# bare_ESP-mainboard.net
KiCad netlist of a schematic drawn in EAGLE
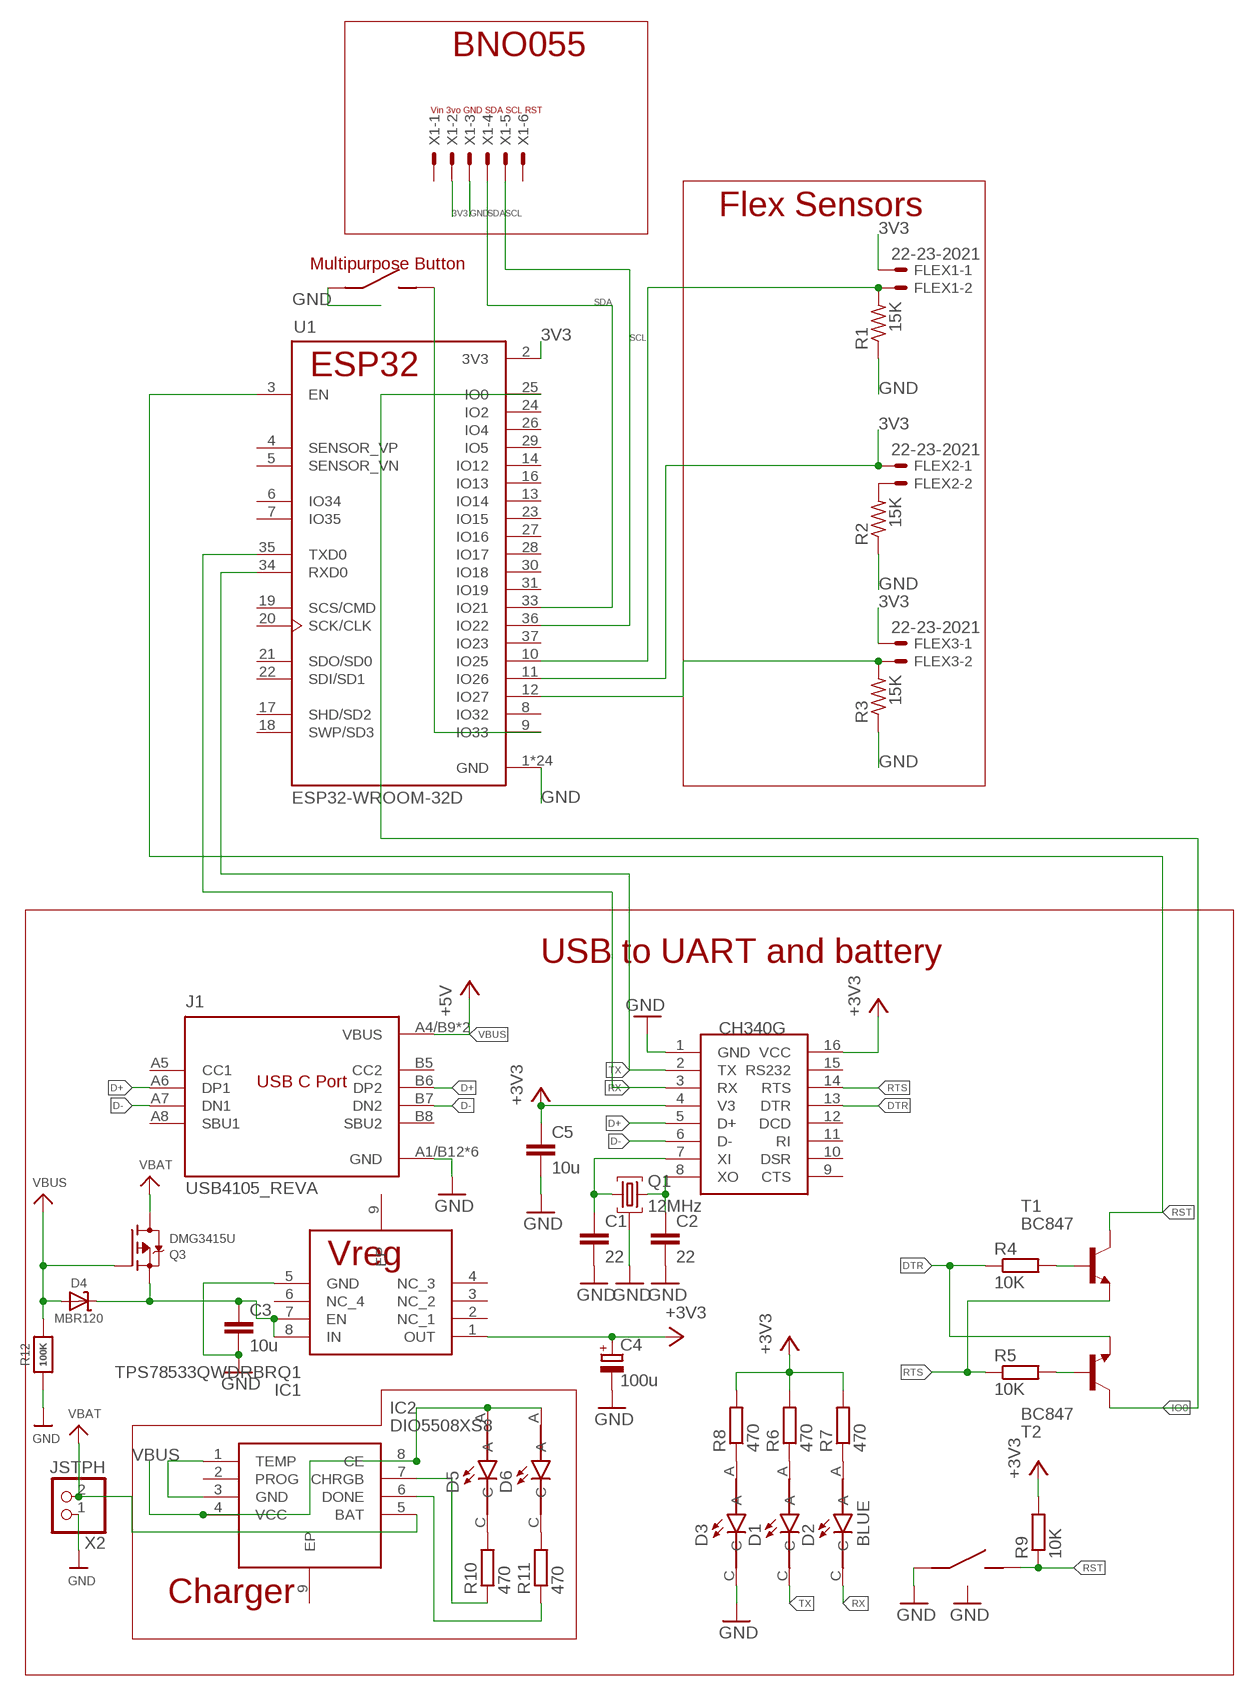
[diagram p0: schematic, sheet 1]

(export (version "E")
  (design (tool "Eeschema 10.0.6"))
  (components
    (comp (ref "BTN1")
      (value "TS36CA-0.7")
      (footprint "eagle-import:SMD")
      (fields (field (name "MF") "SHOU HAN"))
      (libsource (lib "eagle-import") (part "TS36CA-0.7"))
    )
    (comp (ref "BTN2")
      (value "TS36CA-0.7")
      (footprint "eagle-import:SMD")
      (fields (field (name "MF") "SHOU HAN"))
      (libsource (lib "eagle-import") (part "TS36CA-0.7"))
    )
    (comp (ref "C1")
      (value "22")
      (footprint "eagle-import:C0603")
      (libsource (lib "eagle-import") (part "C-EUC0603"))
    )
    (comp (ref "C2")
      (value "22")
      (footprint "eagle-import:C0603")
      (libsource (lib "eagle-import") (part "C-EUC0603"))
    )
    (comp (ref "C3")
      (value "10u")
      (footprint "eagle-import:C0603")
      (libsource (lib "eagle-import") (part "C-EUC0603"))
    )
    (comp (ref "C4")
      (value "100u")
      (footprint "eagle-import:B_3528-21W")
      (libsource (lib "eagle-import") (part "CPOL-EUB/3528-21W"))
    )
    (comp (ref "C5")
      (value "10u")
      (footprint "eagle-import:C0603")
      (libsource (lib "eagle-import") (part "C-EUC0603"))
    )
    (comp (ref "D1")
      (value "BLUE")
      (footprint "eagle-import:LEDC2012X70N")
      (fields (field (name "MF") "Dialight") (field (name "MP") "597-5311-402F"))
      (libsource (lib "eagle-import") (part "597-5311-402F"))
    )
    (comp (ref "D2")
      (value "BLUE")
      (footprint "eagle-import:LEDC2012X70N")
      (fields (field (name "MF") "Dialight") (field (name "MP") "597-5311-402F"))
      (libsource (lib "eagle-import") (part "597-5311-402F"))
    )
    (comp (ref "D3")
      (value "GREEN")
      (footprint "eagle-import:LEDC2012X70N")
      (fields (field (name "MF") "Dialight") (field (name "MP") "597-5311-402F"))
      (libsource (lib "eagle-import") (part "597-5311-402F"))
    )
    (comp (ref "D4")
      (value "MBR120")
      (footprint "eagle-import:SOD-123")
      (libsource (lib "eagle-import") (part "DIODE-SCHOTTKYSOD-123"))
    )
    (comp (ref "D5")
      (value "GREEN")
      (footprint "eagle-import:LEDC2012X70N")
      (fields (field (name "MF") "Dialight") (field (name "MP") "597-5311-402F"))
      (libsource (lib "eagle-import") (part "597-5311-402F"))
    )
    (comp (ref "D6")
      (value "GREEN")
      (footprint "eagle-import:LEDC2012X70N")
      (fields (field (name "MF") "Dialight") (field (name "MP") "597-5311-402F"))
      (libsource (lib "eagle-import") (part "597-5311-402F"))
    )
    (comp (ref "FLEX1")
      (value "22-23-2021")
      (footprint "eagle-import:22-23-2021")
      (fields (field (name "MF") "MOLEX"))
      (libsource (lib "eagle-import") (part "22-23-2021"))
    )
    (comp (ref "FLEX2")
      (value "22-23-2021")
      (footprint "eagle-import:22-23-2021")
      (fields (field (name "MF") "MOLEX"))
      (libsource (lib "eagle-import") (part "22-23-2021"))
    )
    (comp (ref "FLEX3")
      (value "22-23-2021")
      (footprint "eagle-import:22-23-2021")
      (fields (field (name "MF") "MOLEX"))
      (libsource (lib "eagle-import") (part "22-23-2021"))
    )
    (comp (ref "IC1")
      (value "TPS78533QWDRBRQ1")
      (footprint "eagle-import:SON65P300X300X100-9N")
      (fields (field (name "MOUSER_PART_NUMBER") "595-TPS78533QWDRBRQ1"))
      (libsource (lib "eagle-import") (part "TPS78533QWDRBRQ1"))
    )
    (comp (ref "IC2")
      (value "DIO5508XS8")
      (footprint "eagle-import:SOIC127P600X170-9N")
      (fields (field (name "MOUSER_PART_NUMBER") "453-DIO5508XS8"))
      (libsource (lib "eagle-import") (part "DIO5508XS8"))
    )
    (comp (ref "J1")
      (value "USB4105_REVA")
      (footprint "eagle-import:GCT_USB4105_REVA")
      (fields (field (name "MF") "Global Connector Technology") (field (name "MP") "USB4105"))
      (libsource (lib "eagle-import") (part "USB4105_REVA"))
    )
    (comp (ref "Q1")
      (value "12MHz")
      (footprint "eagle-import:SMD3225")
      (fields (field (name "MF") "Yangxing Tech") (field (name "MP") "X322512MSB4SI"))
      (libsource (lib "eagle-import") (part "YSX321SL"))
    )
    (comp (ref "Q3")
      (value "DMG3415U")
      (footprint "eagle-import:SOT23-R")
      (libsource (lib "eagle-import") (part "MOSFET-P"))
    )
    (comp (ref "R1")
      (value "15K")
      (footprint "eagle-import:0805-THM")
      (libsource (lib "eagle-import") (part "FLIPFLOP-RES"))
    )
    (comp (ref "R2")
      (value "15K")
      (footprint "eagle-import:0805-THM")
      (libsource (lib "eagle-import") (part "FLIPFLOP-RES"))
    )
    (comp (ref "R3")
      (value "15K")
      (footprint "eagle-import:0805-THM")
      (libsource (lib "eagle-import") (part "FLIPFLOP-RES"))
    )
    (comp (ref "R4")
      (value "10K")
      (footprint "eagle-import:R0603")
      (libsource (lib "eagle-import") (part "R-EU_R0603"))
    )
    (comp (ref "R5")
      (value "10K")
      (footprint "eagle-import:R0603")
      (libsource (lib "eagle-import") (part "R-EU_R0603"))
    )
    (comp (ref "R6")
      (value "470")
      (footprint "eagle-import:R0603")
      (libsource (lib "eagle-import") (part "R-EU_R0603"))
    )
    (comp (ref "R7")
      (value "470")
      (footprint "eagle-import:R0603")
      (libsource (lib "eagle-import") (part "R-EU_R0603"))
    )
    (comp (ref "R8")
      (value "470")
      (footprint "eagle-import:R0603")
      (libsource (lib "eagle-import") (part "R-EU_R0603"))
    )
    (comp (ref "R9")
      (value "10K")
      (footprint "eagle-import:R0603")
      (libsource (lib "eagle-import") (part "R-EU_R0603"))
    )
    (comp (ref "R10")
      (value "470")
      (footprint "eagle-import:R0603")
      (libsource (lib "eagle-import") (part "R-EU_R0603"))
    )
    (comp (ref "R11")
      (value "470")
      (footprint "eagle-import:R0603")
      (libsource (lib "eagle-import") (part "R-EU_R0603"))
    )
    (comp (ref "R12")
      (value "100K")
      (footprint "eagle-import:0603-NO")
      (libsource (lib "eagle-import") (part "RESISTOR_0603_NOOUT"))
    )
    (comp (ref "T1")
      (value "BC847")
      (footprint "eagle-import:SOT23")
      (libsource (lib "eagle-import") (part "BC847"))
    )
    (comp (ref "T2")
      (value "BC847")
      (footprint "eagle-import:SOT23")
      (libsource (lib "eagle-import") (part "BC847"))
    )
    (comp (ref "U1")
      (value "ESP32-WROOM-32D")
      (footprint "eagle-import:MODULE_ESP32-WROOM-32D")
      (fields (field (name "MF") "Espressif Systems"))
      (libsource (lib "eagle-import") (part "ESP32-WROOM-32D"))
    )
    (comp (ref "U2")
      (value "CH340G")
      (footprint "eagle-import:SOIC16")
      (libsource (lib "eagle-import") (part "CH340G"))
    )
    (comp (ref "X1")
      (value "22-23-2061")
      (footprint "eagle-import:22-23-2061")
      (fields (field (name "MF") "MOLEX"))
      (libsource (lib "eagle-import") (part "22-23-2061"))
    )
    (comp (ref "X2")
      (value "JSTPH")
      (footprint "eagle-import:JSTPH2")
      (libsource (lib "eagle-import") (part "CON_JST_PH_2PIN"))
    )
  )
  (nets
    (net (code "1") (name "+3V3") (class "Default")
      (node (ref "C4") (pin "+") (pinfunction "+_+") (pintype "passive"))
      (node (ref "C5") (pin "1") (pinfunction "1_1") (pintype "passive"))
      (node (ref "IC1") (pin "1") (pinfunction "OUT_1") (pintype "bidirectional"))
      (node (ref "R6") (pin "2") (pinfunction "2_2") (pintype "passive"))
      (node (ref "R7") (pin "2") (pinfunction "2_2") (pintype "passive"))
      (node (ref "R8") (pin "2") (pinfunction "2_2") (pintype "passive"))
      (node (ref "R9") (pin "2") (pinfunction "2_2") (pintype "passive"))
      (node (ref "U2") (pin "16") (pinfunction "VCC_16") (pintype "bidirectional"))
      (node (ref "U2") (pin "4") (pinfunction "V3_4") (pintype "bidirectional"))
    )
    (net (code "2") (name "/3V3") (class "Default")
      (node (ref "FLEX1") (pin "1") (pinfunction "S_1") (pintype "passive"))
      (node (ref "FLEX2") (pin "1") (pinfunction "S_1") (pintype "passive"))
      (node (ref "FLEX3") (pin "1") (pinfunction "S_1") (pintype "passive"))
      (node (ref "U1") (pin "11") (pinfunction "IO26_11") (pintype "bidirectional"))
      (node (ref "U1") (pin "2") (pinfunction "3V3_2") (pintype "power_in"))
      (node (ref "X1") (pin "2") (pinfunction "S_2") (pintype "passive"))
    )
    (net (code "3") (name "/SCL") (class "Default")
      (node (ref "U1") (pin "36") (pinfunction "IO22_36") (pintype "bidirectional"))
      (node (ref "X1") (pin "5") (pinfunction "S_5") (pintype "passive"))
    )
    (net (code "4") (name "/SDA") (class "Default")
      (node (ref "U1") (pin "33") (pinfunction "IO21_33") (pintype "bidirectional"))
      (node (ref "X1") (pin "4") (pinfunction "S_4") (pintype "passive"))
    )
    (net (code "5") (name "D+") (class "Default")
      (node (ref "J1") (pin "A6") (pinfunction "DP1_A6") (pintype "bidirectional"))
      (node (ref "J1") (pin "B6") (pinfunction "DP2_B6") (pintype "bidirectional"))
      (node (ref "U2") (pin "5") (pinfunction "D+_5") (pintype "bidirectional"))
    )
    (net (code "6") (name "D-") (class "Default")
      (node (ref "J1") (pin "A7") (pinfunction "DN1_A7") (pintype "bidirectional"))
      (node (ref "J1") (pin "B7") (pinfunction "DN2_B7") (pintype "bidirectional"))
      (node (ref "U2") (pin "6") (pinfunction "D-_6") (pintype "bidirectional"))
    )
    (net (code "7") (name "DTR") (class "Default")
      (node (ref "R4") (pin "1") (pinfunction "1_1") (pintype "passive"))
      (node (ref "T2") (pin "2") (pinfunction "E_2") (pintype "passive"))
      (node (ref "U2") (pin "13") (pinfunction "DTR_13") (pintype "bidirectional"))
    )
    (net (code "8") (name "GND") (class "Default")
      (node (ref "BTN1") (pin "A") (pinfunction "CASE_A") (pintype "power_in"))
      (node (ref "BTN1") (pin "B") (pinfunction "CASE_B") (pintype "power_in"))
      (node (ref "BTN1") (pin "C") (pinfunction "P$1_C") (pintype "bidirectional"))
      (node (ref "BTN2") (pin "A") (pinfunction "CASE_A") (pintype "power_in"))
      (node (ref "BTN2") (pin "B") (pinfunction "CASE_B") (pintype "power_in"))
      (node (ref "BTN2") (pin "C") (pinfunction "P$1_C") (pintype "bidirectional"))
      (node (ref "C1") (pin "2") (pinfunction "2_2") (pintype "passive"))
      (node (ref "C2") (pin "2") (pinfunction "2_2") (pintype "passive"))
      (node (ref "C3") (pin "2") (pinfunction "2_2") (pintype "passive"))
      (node (ref "C4") (pin "-") (pinfunction "-_-") (pintype "passive"))
      (node (ref "C5") (pin "2") (pinfunction "2_2") (pintype "passive"))
      (node (ref "D3") (pin "C") (pinfunction "C_C") (pintype "passive"))
      (node (ref "IC1") (pin "5") (pinfunction "GND_5") (pintype "bidirectional"))
      (node (ref "J1") (pin "A1/B12") (pinfunction "GND_A1/B12") (pintype "power_in"))
      (node (ref "J1") (pin "B1/A12") (pinfunction "GND_B1/A12") (pintype "power_in"))
      (node (ref "J1") (pin "G1") (pinfunction "GND_G1") (pintype "power_in"))
      (node (ref "J1") (pin "G2") (pinfunction "GND_G2") (pintype "power_in"))
      (node (ref "J1") (pin "G3") (pinfunction "GND_G3") (pintype "power_in"))
      (node (ref "J1") (pin "G4") (pinfunction "GND_G4") (pintype "power_in"))
      (node (ref "Q1") (pin "P$2") (pinfunction "CASE_P$2") (pintype "power_in"))
      (node (ref "Q1") (pin "P$4") (pinfunction "CASE_P$4") (pintype "power_in"))
      (node (ref "R1") (pin "1") (pinfunction "1_1") (pintype "passive"))
      (node (ref "R12") (pin "1") (pinfunction "1_1") (pintype "passive"))
      (node (ref "R2") (pin "1") (pinfunction "1_1") (pintype "passive"))
      (node (ref "R3") (pin "1") (pinfunction "1_1") (pintype "passive"))
      (node (ref "U1") (pin "1") (pinfunction "GND_1") (pintype "power_in"))
      (node (ref "U1") (pin "15") (pinfunction "GND_15") (pintype "power_in"))
      (node (ref "U1") (pin "38") (pinfunction "GND_38") (pintype "power_in"))
      (node (ref "U1") (pin "39_1") (pinfunction "GND_39_1") (pintype "power_in"))
      (node (ref "U1") (pin "39_10") (pinfunction "GND_39_10") (pintype "power_in"))
      (node (ref "U1") (pin "39_11") (pinfunction "GND_39_11") (pintype "power_in"))
      (node (ref "U1") (pin "39_12") (pinfunction "GND_39_12") (pintype "power_in"))
      (node (ref "U1") (pin "39_13") (pinfunction "GND_39_13") (pintype "power_in"))
      (node (ref "U1") (pin "39_14") (pinfunction "GND_39_14") (pintype "power_in"))
      (node (ref "U1") (pin "39_15") (pinfunction "GND_39_15") (pintype "power_in"))
      (node (ref "U1") (pin "39_16") (pinfunction "GND_39_16") (pintype "power_in"))
      (node (ref "U1") (pin "39_17") (pinfunction "GND_39_17") (pintype "power_in"))
      (node (ref "U1") (pin "39_18") (pinfunction "GND_39_18") (pintype "power_in"))
      (node (ref "U1") (pin "39_19") (pinfunction "GND_39_19") (pintype "power_in"))
      (node (ref "U1") (pin "39_2") (pinfunction "GND_39_2") (pintype "power_in"))
      (node (ref "U1") (pin "39_20") (pinfunction "GND_39_20") (pintype "power_in"))
      (node (ref "U1") (pin "39_21") (pinfunction "GND_39_21") (pintype "power_in"))
      (node (ref "U1") (pin "39_3") (pinfunction "GND_39_3") (pintype "power_in"))
      (node (ref "U1") (pin "39_4") (pinfunction "GND_39_4") (pintype "power_in"))
      (node (ref "U1") (pin "39_5") (pinfunction "GND_39_5") (pintype "power_in"))
      (node (ref "U1") (pin "39_6") (pinfunction "GND_39_6") (pintype "power_in"))
      (node (ref "U1") (pin "39_7") (pinfunction "GND_39_7") (pintype "power_in"))
      (node (ref "U1") (pin "39_8") (pinfunction "GND_39_8") (pintype "power_in"))
      (node (ref "U1") (pin "39_9") (pinfunction "GND_39_9") (pintype "power_in"))
      (node (ref "U2") (pin "1") (pinfunction "GND_1") (pintype "bidirectional"))
      (node (ref "X1") (pin "3") (pinfunction "S_3") (pintype "passive"))
      (node (ref "X2") (pin "1") (pinfunction "1_1") (pintype "passive"))
    )
    (net (code "9") (name "IO0") (class "Default")
      (node (ref "T2") (pin "3") (pinfunction "C_3") (pintype "passive"))
      (node (ref "U1") (pin "25") (pinfunction "IO0_25") (pintype "bidirectional"))
    )
    (net (code "10") (name "Net-(BTN2-P$2)") (class "Default")
      (node (ref "BTN2") (pin "D") (pinfunction "P$2_D") (pintype "bidirectional"))
      (node (ref "U1") (pin "9") (pinfunction "IO33_9") (pintype "bidirectional"))
    )
    (net (code "11") (name "Net-(D1-PadA)") (class "Default")
      (node (ref "D1") (pin "A") (pinfunction "A_A") (pintype "passive"))
      (node (ref "R6") (pin "1") (pinfunction "1_1") (pintype "passive"))
    )
    (net (code "12") (name "Net-(D2-PadA)") (class "Default")
      (node (ref "D2") (pin "A") (pinfunction "A_A") (pintype "passive"))
      (node (ref "R7") (pin "1") (pinfunction "1_1") (pintype "passive"))
    )
    (net (code "13") (name "Net-(D3-PadA)") (class "Default")
      (node (ref "D3") (pin "A") (pinfunction "A_A") (pintype "passive"))
      (node (ref "R8") (pin "1") (pinfunction "1_1") (pintype "passive"))
    )
    (net (code "14") (name "Net-(D5-PadC)") (class "Default")
      (node (ref "D5") (pin "C") (pinfunction "C_C") (pintype "passive"))
      (node (ref "R10") (pin "2") (pinfunction "2_2") (pintype "passive"))
    )
    (net (code "15") (name "Net-(D6-PadC)") (class "Default")
      (node (ref "D6") (pin "C") (pinfunction "C_C") (pintype "passive"))
      (node (ref "R11") (pin "2") (pinfunction "2_2") (pintype "passive"))
    )
    (net (code "16") (name "Net-(FLEX1B-S)") (class "Default")
      (node (ref "FLEX1") (pin "2") (pinfunction "S_2") (pintype "passive"))
      (node (ref "R1") (pin "2") (pinfunction "2_2") (pintype "passive"))
      (node (ref "U1") (pin "10") (pinfunction "IO25_10") (pintype "bidirectional"))
    )
    (net (code "17") (name "Net-(FLEX2B-S)") (class "Default")
      (node (ref "FLEX2") (pin "2") (pinfunction "S_2") (pintype "passive"))
      (node (ref "R2") (pin "2") (pinfunction "2_2") (pintype "passive"))
    )
    (net (code "18") (name "Net-(FLEX3B-S)") (class "Default")
      (node (ref "FLEX3") (pin "2") (pinfunction "S_2") (pintype "passive"))
      (node (ref "R3") (pin "2") (pinfunction "2_2") (pintype "passive"))
      (node (ref "U1") (pin "12") (pinfunction "IO27_12") (pintype "bidirectional"))
    )
    (net (code "19") (name "Net-(IC1-EN)") (class "Default")
      (node (ref "C3") (pin "1") (pinfunction "1_1") (pintype "passive"))
      (node (ref "D4") (pin "C") (pinfunction "C_C") (pintype "passive"))
      (node (ref "IC1") (pin "7") (pinfunction "EN_7") (pintype "bidirectional"))
      (node (ref "IC1") (pin "8") (pinfunction "IN_8") (pintype "bidirectional"))
      (node (ref "Q3") (pin "2") (pinfunction "S_2") (pintype "passive"))
    )
    (net (code "20") (name "Net-(IC2-CHRGB)") (class "Default")
      (node (ref "IC2") (pin "7") (pinfunction "CHRGB_7") (pintype "bidirectional"))
      (node (ref "R10") (pin "1") (pinfunction "1_1") (pintype "passive"))
    )
    (net (code "21") (name "Net-(IC2-DONE)") (class "Default")
      (node (ref "IC2") (pin "6") (pinfunction "DONE_6") (pintype "bidirectional"))
      (node (ref "R11") (pin "1") (pinfunction "1_1") (pintype "passive"))
    )
    (net (code "22") (name "Net-(IC2-GND)") (class "Default")
      (node (ref "IC2") (pin "1") (pinfunction "TEMP_1") (pintype "bidirectional"))
      (node (ref "IC2") (pin "3") (pinfunction "GND_3") (pintype "bidirectional"))
    )
    (net (code "23") (name "Net-(Q1-1)") (class "Default")
      (node (ref "C1") (pin "1") (pinfunction "1_1") (pintype "passive"))
      (node (ref "Q1") (pin "P$1") (pinfunction "1_P$1") (pintype "passive"))
      (node (ref "U2") (pin "7") (pinfunction "XI_7") (pintype "bidirectional"))
    )
    (net (code "24") (name "Net-(Q1-2)") (class "Default")
      (node (ref "C2") (pin "1") (pinfunction "1_1") (pintype "passive"))
      (node (ref "Q1") (pin "P$3") (pinfunction "2_P$3") (pintype "passive"))
      (node (ref "U2") (pin "8") (pinfunction "XO_8") (pintype "bidirectional"))
    )
    (net (code "25") (name "Net-(T1-B)") (class "Default")
      (node (ref "R4") (pin "2") (pinfunction "2_2") (pintype "passive"))
      (node (ref "T1") (pin "1") (pinfunction "B_1") (pintype "passive"))
    )
    (net (code "26") (name "Net-(T2-B)") (class "Default")
      (node (ref "R5") (pin "2") (pinfunction "2_2") (pintype "passive"))
      (node (ref "T2") (pin "1") (pinfunction "B_1") (pintype "passive"))
    )
    (net (code "27") (name "RST") (class "Default")
      (node (ref "BTN1") (pin "D") (pinfunction "P$2_D") (pintype "bidirectional"))
      (node (ref "R9") (pin "1") (pinfunction "1_1") (pintype "passive"))
      (node (ref "T1") (pin "3") (pinfunction "C_3") (pintype "passive"))
      (node (ref "U1") (pin "3") (pinfunction "EN_3") (pintype "input"))
    )
    (net (code "28") (name "RTS") (class "Default")
      (node (ref "R5") (pin "1") (pinfunction "1_1") (pintype "passive"))
      (node (ref "T1") (pin "2") (pinfunction "E_2") (pintype "passive"))
      (node (ref "U2") (pin "14") (pinfunction "RTS_14") (pintype "bidirectional"))
    )
    (net (code "29") (name "RX") (class "Default")
      (node (ref "D2") (pin "C") (pinfunction "C_C") (pintype "passive"))
      (node (ref "U1") (pin "35") (pinfunction "TXD0_35") (pintype "bidirectional"))
      (node (ref "U2") (pin "3") (pinfunction "RX_3") (pintype "bidirectional"))
    )
    (net (code "30") (name "TX") (class "Default")
      (node (ref "D1") (pin "C") (pinfunction "C_C") (pintype "passive"))
      (node (ref "U1") (pin "34") (pinfunction "RXD0_34") (pintype "bidirectional"))
      (node (ref "U2") (pin "2") (pinfunction "TX_2") (pintype "bidirectional"))
    )
    (net (code "31") (name "VBAT") (class "Default")
      (node (ref "IC2") (pin "5") (pinfunction "BAT_5") (pintype "bidirectional"))
      (node (ref "Q3") (pin "3") (pinfunction "D_3") (pintype "passive"))
      (node (ref "X2") (pin "2") (pinfunction "2_2") (pintype "passive"))
    )
    (net (code "32") (name "VBUS") (class "Default")
      (node (ref "D4") (pin "A") (pinfunction "A_A") (pintype "passive"))
      (node (ref "D5") (pin "A") (pinfunction "A_A") (pintype "passive"))
      (node (ref "D6") (pin "A") (pinfunction "A_A") (pintype "passive"))
      (node (ref "IC2") (pin "4") (pinfunction "VCC_4") (pintype "bidirectional"))
      (node (ref "IC2") (pin "8") (pinfunction "CE_8") (pintype "bidirectional"))
      (node (ref "J1") (pin "A4/B9") (pinfunction "VBUS_A4/B9") (pintype "power_in"))
      (node (ref "J1") (pin "B4/A9") (pinfunction "VBUS_B4/A9") (pintype "power_in"))
      (node (ref "Q3") (pin "1") (pinfunction "G_1") (pintype "passive"))
      (node (ref "R12") (pin "2") (pinfunction "2_2") (pintype "passive"))
    )
    (net (code "33") (name "unconnected-(IC1-EP-Pad9)") (class "Default")
      (node (ref "IC1") (pin "9") (pinfunction "EP_9") (pintype "bidirectional"))
    )
    (net (code "34") (name "unconnected-(IC1-NC_1-Pad2)") (class "Default")
      (node (ref "IC1") (pin "2") (pinfunction "NC_1_2") (pintype "bidirectional"))
    )
    (net (code "35") (name "unconnected-(IC1-NC_2-Pad3)") (class "Default")
      (node (ref "IC1") (pin "3") (pinfunction "NC_2_3") (pintype "bidirectional"))
    )
    (net (code "36") (name "unconnected-(IC1-NC_3-Pad4)") (class "Default")
      (node (ref "IC1") (pin "4") (pinfunction "NC_3_4") (pintype "bidirectional"))
    )
    (net (code "37") (name "unconnected-(IC1-NC_4-Pad6)") (class "Default")
      (node (ref "IC1") (pin "6") (pinfunction "NC_4_6") (pintype "bidirectional"))
    )
    (net (code "38") (name "unconnected-(IC2-EP-Pad9)") (class "Default")
      (node (ref "IC2") (pin "9") (pinfunction "EP_9") (pintype "bidirectional"))
    )
    (net (code "39") (name "unconnected-(IC2-PROG-Pad2)") (class "Default")
      (node (ref "IC2") (pin "2") (pinfunction "PROG_2") (pintype "bidirectional"))
    )
    (net (code "40") (name "unconnected-(J1-CC1-PadA5)") (class "Default")
      (node (ref "J1") (pin "A5") (pinfunction "CC1_A5") (pintype "bidirectional"))
    )
    (net (code "41") (name "unconnected-(J1-CC2-PadB5)") (class "Default")
      (node (ref "J1") (pin "B5") (pinfunction "CC2_B5") (pintype "bidirectional"))
    )
    (net (code "42") (name "unconnected-(J1-SBU1-PadA8)") (class "Default")
      (node (ref "J1") (pin "A8") (pinfunction "SBU1_A8") (pintype "bidirectional"))
    )
    (net (code "43") (name "unconnected-(J1-SBU2-PadB8)") (class "Default")
      (node (ref "J1") (pin "B8") (pinfunction "SBU2_B8") (pintype "bidirectional"))
    )
    (net (code "44") (name "unconnected-(U1-IO2-Pad24)") (class "Default")
      (node (ref "U1") (pin "24") (pinfunction "IO2_24") (pintype "bidirectional"))
    )
    (net (code "45") (name "unconnected-(U1-IO4-Pad26)") (class "Default")
      (node (ref "U1") (pin "26") (pinfunction "IO4_26") (pintype "bidirectional"))
    )
    (net (code "46") (name "unconnected-(U1-IO5-Pad29)") (class "Default")
      (node (ref "U1") (pin "29") (pinfunction "IO5_29") (pintype "bidirectional"))
    )
    (net (code "47") (name "unconnected-(U1-IO12-Pad14)") (class "Default")
      (node (ref "U1") (pin "14") (pinfunction "IO12_14") (pintype "bidirectional"))
    )
    (net (code "48") (name "unconnected-(U1-IO13-Pad16)") (class "Default")
      (node (ref "U1") (pin "16") (pinfunction "IO13_16") (pintype "bidirectional"))
    )
    (net (code "49") (name "unconnected-(U1-IO14-Pad13)") (class "Default")
      (node (ref "U1") (pin "13") (pinfunction "IO14_13") (pintype "bidirectional"))
    )
    (net (code "50") (name "unconnected-(U1-IO15-Pad23)") (class "Default")
      (node (ref "U1") (pin "23") (pinfunction "IO15_23") (pintype "bidirectional"))
    )
    (net (code "51") (name "unconnected-(U1-IO16-Pad27)") (class "Default")
      (node (ref "U1") (pin "27") (pinfunction "IO16_27") (pintype "bidirectional"))
    )
    (net (code "52") (name "unconnected-(U1-IO17-Pad28)") (class "Default")
      (node (ref "U1") (pin "28") (pinfunction "IO17_28") (pintype "bidirectional"))
    )
    (net (code "53") (name "unconnected-(U1-IO18-Pad30)") (class "Default")
      (node (ref "U1") (pin "30") (pinfunction "IO18_30") (pintype "bidirectional"))
    )
    (net (code "54") (name "unconnected-(U1-IO19-Pad31)") (class "Default")
      (node (ref "U1") (pin "31") (pinfunction "IO19_31") (pintype "bidirectional"))
    )
    (net (code "55") (name "unconnected-(U1-IO23-Pad37)") (class "Default")
      (node (ref "U1") (pin "37") (pinfunction "IO23_37") (pintype "bidirectional"))
    )
    (net (code "56") (name "unconnected-(U1-IO32-Pad8)") (class "Default")
      (node (ref "U1") (pin "8") (pinfunction "IO32_8") (pintype "bidirectional"))
    )
    (net (code "57") (name "unconnected-(U1-IO34-Pad6)") (class "Default")
      (node (ref "U1") (pin "6") (pinfunction "IO34_6") (pintype "input"))
    )
    (net (code "58") (name "unconnected-(U1-IO35-Pad7)") (class "Default")
      (node (ref "U1") (pin "7") (pinfunction "IO35_7") (pintype "input"))
    )
    (net (code "59") (name "unconnected-(U1-SCK{slash}CLK-Pad20)") (class "Default")
      (node (ref "U1") (pin "20") (pinfunction "SCK/CLK_20") (pintype "bidirectional"))
    )
    (net (code "60") (name "unconnected-(U1-SCS{slash}CMD-Pad19)") (class "Default")
      (node (ref "U1") (pin "19") (pinfunction "SCS/CMD_19") (pintype "bidirectional"))
    )
    (net (code "61") (name "unconnected-(U1-SDI{slash}SD1-Pad22)") (class "Default")
      (node (ref "U1") (pin "22") (pinfunction "SDI/SD1_22") (pintype "bidirectional"))
    )
    (net (code "62") (name "unconnected-(U1-SDO{slash}SD0-Pad21)") (class "Default")
      (node (ref "U1") (pin "21") (pinfunction "SDO/SD0_21") (pintype "bidirectional"))
    )
    (net (code "63") (name "unconnected-(U1-SENSOR_VN-Pad5)") (class "Default")
      (node (ref "U1") (pin "5") (pinfunction "SENSOR_VN_5") (pintype "input"))
    )
    (net (code "64") (name "unconnected-(U1-SENSOR_VP-Pad4)") (class "Default")
      (node (ref "U1") (pin "4") (pinfunction "SENSOR_VP_4") (pintype "input"))
    )
    (net (code "65") (name "unconnected-(U1-SHD{slash}SD2-Pad17)") (class "Default")
      (node (ref "U1") (pin "17") (pinfunction "SHD/SD2_17") (pintype "bidirectional"))
    )
    (net (code "66") (name "unconnected-(U1-SWP{slash}SD3-Pad18)") (class "Default")
      (node (ref "U1") (pin "18") (pinfunction "SWP/SD3_18") (pintype "bidirectional"))
    )
    (net (code "67") (name "unconnected-(U2-CTS-Pad9)") (class "Default")
      (node (ref "U2") (pin "9") (pinfunction "CTS_9") (pintype "bidirectional"))
    )
    (net (code "68") (name "unconnected-(U2-DCD-Pad12)") (class "Default")
      (node (ref "U2") (pin "12") (pinfunction "DCD_12") (pintype "bidirectional"))
    )
    (net (code "69") (name "unconnected-(U2-DSR-Pad10)") (class "Default")
      (node (ref "U2") (pin "10") (pinfunction "DSR_10") (pintype "bidirectional"))
    )
    (net (code "70") (name "unconnected-(U2-RI-Pad11)") (class "Default")
      (node (ref "U2") (pin "11") (pinfunction "RI_11") (pintype "bidirectional"))
    )
    (net (code "71") (name "unconnected-(U2-RS232-Pad15)") (class "Default")
      (node (ref "U2") (pin "15") (pinfunction "RS232_15") (pintype "bidirectional"))
    )
    (net (code "72") (name "unconnected-(X1A-S-Pad1)") (class "Default")
      (node (ref "X1") (pin "1") (pinfunction "S_1") (pintype "passive"))
    )
    (net (code "73") (name "unconnected-(X1F-S-Pad6)") (class "Default")
      (node (ref "X1") (pin "6") (pinfunction "S_6") (pintype "passive"))
    )
  )
)
